# SERVODENGEN_ver2.net
KiCad netlist of a schematic drawn in EAGLE
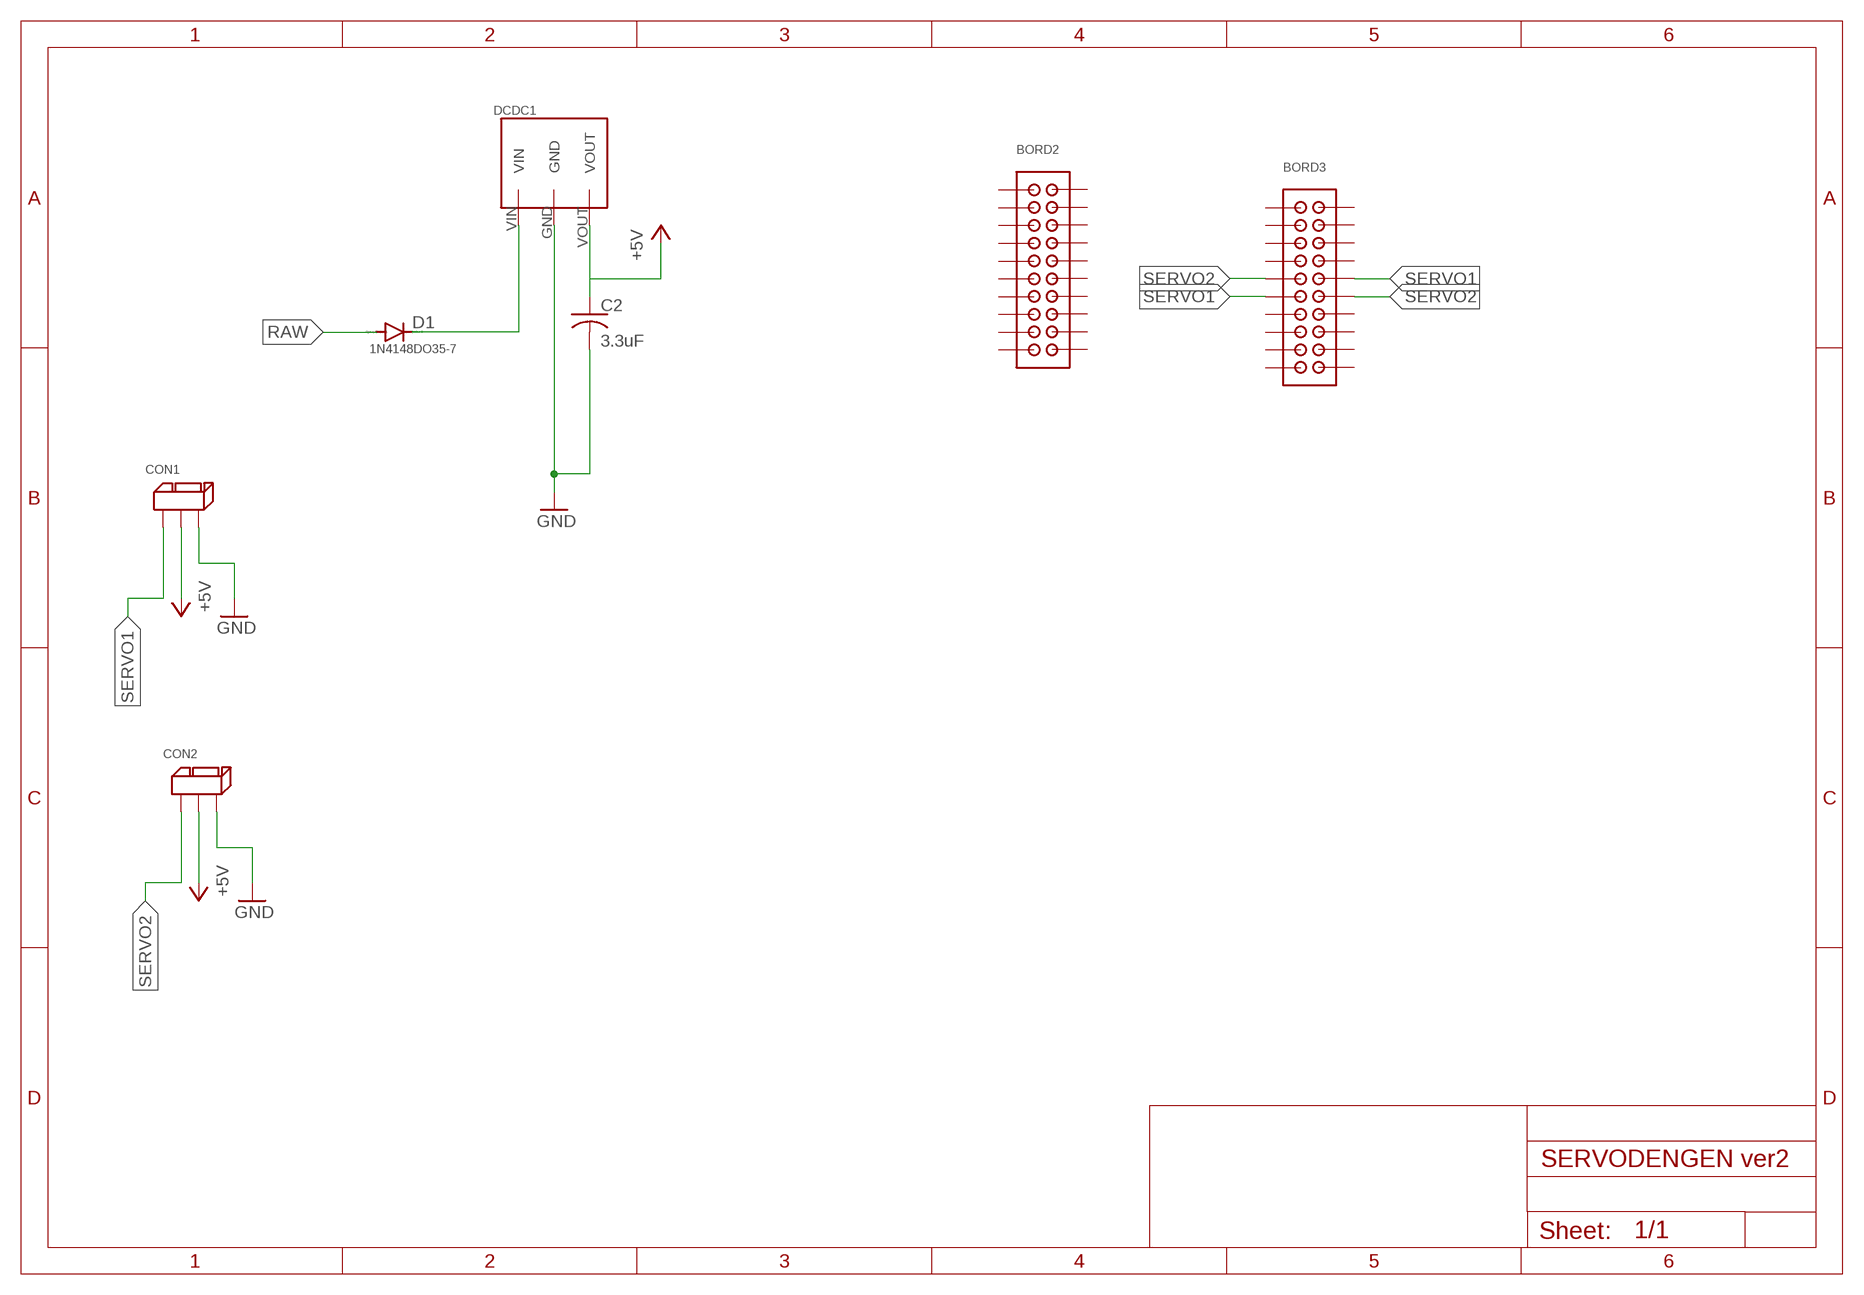
[diagram p0: schematic, sheet 1]

(export (version "E")
  (design (tool "Eeschema 10.0.6"))
  (components
    (comp (ref "BORD2")
      (value "2X10")
      (footprint "eagle-import:2X10")
      (libsource (lib "eagle-import") (part "2X10"))
    )
    (comp (ref "BORD3")
      (value "2X10")
      (footprint "eagle-import:2X10")
      (libsource (lib "eagle-import") (part "2X10"))
    )
    (comp (ref "C2")
      (value "3.3uF")
      (footprint "eagle-import:C0603")
      (libsource (lib "eagle-import") (part "C-USC0603"))
    )
    (comp (ref "CON1")
      (value "3PIN")
      (footprint "eagle-import:3PIN")
      (libsource (lib "eagle-import") (part "3PIN"))
    )
    (comp (ref "CON2")
      (value "3PIN")
      (footprint "eagle-import:3PIN")
      (libsource (lib "eagle-import") (part "3PIN"))
    )
    (comp (ref "D1")
      (value "1N4148DO35-7")
      (footprint "eagle-import:DO35-7")
      (libsource (lib "eagle-import") (part "1N4148DO35-7"))
    )
    (comp (ref "DCDC1")
      (value "5V1A_M78AR05-1")
      (footprint "eagle-import:5V1A_M78AR05-1")
      (libsource (lib "eagle-import") (part "5V1A_M78AR05-1"))
    )
  )
  (nets
    (net (code "1") (name "+5V") (class "Default")
      (node (ref "C2") (pin "1") (pinfunction "1_1") (pintype "passive"))
      (node (ref "CON1") (pin "P$2") (pinfunction "P$2_P$2") (pintype "bidirectional"))
      (node (ref "CON2") (pin "P$2") (pinfunction "P$2_P$2") (pintype "bidirectional"))
      (node (ref "DCDC1") (pin "VOUT") (pinfunction "VOUT_VOUT") (pintype "bidirectional"))
    )
    (net (code "2") (name "GND") (class "Default")
      (node (ref "C2") (pin "2") (pinfunction "2_2") (pintype "passive"))
      (node (ref "CON1") (pin "P$3") (pinfunction "P$3_P$3") (pintype "bidirectional"))
      (node (ref "CON2") (pin "P$3") (pinfunction "P$3_P$3") (pintype "bidirectional"))
      (node (ref "DCDC1") (pin "GND") (pinfunction "GND_GND") (pintype "bidirectional"))
    )
    (net (code "3") (name "RAW") (class "Default")
      (node (ref "D1") (pin "C") (pinfunction "C_C") (pintype "passive"))
      (node (ref "DCDC1") (pin "VIN") (pinfunction "VIN_VIN") (pintype "bidirectional"))
    )
    (net (code "4") (name "SERVO1") (class "Default")
      (node (ref "BORD3") (pin "P$10") (pinfunction "P$10_P$10") (pintype "bidirectional"))
      (node (ref "BORD3") (pin "P$11") (pinfunction "P$11_P$11") (pintype "bidirectional"))
      (node (ref "CON1") (pin "P$1") (pinfunction "P$1_P$1") (pintype "bidirectional"))
    )
    (net (code "5") (name "SERVO2") (class "Default")
      (node (ref "BORD3") (pin "P$12") (pinfunction "P$12_P$12") (pintype "bidirectional"))
      (node (ref "BORD3") (pin "P$9") (pinfunction "P$9_P$9") (pintype "bidirectional"))
      (node (ref "CON2") (pin "P$1") (pinfunction "P$1_P$1") (pintype "bidirectional"))
    )
    (net (code "6") (name "unconnected-(BORD2-PadP$1)") (class "Default")
      (node (ref "BORD2") (pin "P$1") (pinfunction "P$1_P$1") (pintype "bidirectional"))
    )
    (net (code "7") (name "unconnected-(BORD2-PadP$2)") (class "Default")
      (node (ref "BORD2") (pin "P$2") (pinfunction "P$2_P$2") (pintype "bidirectional"))
    )
    (net (code "8") (name "unconnected-(BORD2-PadP$3)") (class "Default")
      (node (ref "BORD2") (pin "P$3") (pinfunction "P$3_P$3") (pintype "bidirectional"))
    )
    (net (code "9") (name "unconnected-(BORD2-PadP$4)") (class "Default")
      (node (ref "BORD2") (pin "P$4") (pinfunction "P$4_P$4") (pintype "bidirectional"))
    )
    (net (code "10") (name "unconnected-(BORD2-PadP$5)") (class "Default")
      (node (ref "BORD2") (pin "P$5") (pinfunction "P$5_P$5") (pintype "bidirectional"))
    )
    (net (code "11") (name "unconnected-(BORD2-PadP$6)") (class "Default")
      (node (ref "BORD2") (pin "P$6") (pinfunction "P$6_P$6") (pintype "bidirectional"))
    )
    (net (code "12") (name "unconnected-(BORD2-PadP$7)") (class "Default")
      (node (ref "BORD2") (pin "P$7") (pinfunction "P$7_P$7") (pintype "bidirectional"))
    )
    (net (code "13") (name "unconnected-(BORD2-PadP$8)") (class "Default")
      (node (ref "BORD2") (pin "P$8") (pinfunction "P$8_P$8") (pintype "bidirectional"))
    )
    (net (code "14") (name "unconnected-(BORD2-PadP$9)") (class "Default")
      (node (ref "BORD2") (pin "P$9") (pinfunction "P$9_P$9") (pintype "bidirectional"))
    )
    (net (code "15") (name "unconnected-(BORD2-PadP$10)") (class "Default")
      (node (ref "BORD2") (pin "P$10") (pinfunction "P$10_P$10") (pintype "bidirectional"))
    )
    (net (code "16") (name "unconnected-(BORD2-PadP$11)") (class "Default")
      (node (ref "BORD2") (pin "P$11") (pinfunction "P$11_P$11") (pintype "bidirectional"))
    )
    (net (code "17") (name "unconnected-(BORD2-PadP$12)") (class "Default")
      (node (ref "BORD2") (pin "P$12") (pinfunction "P$12_P$12") (pintype "bidirectional"))
    )
    (net (code "18") (name "unconnected-(BORD2-PadP$13)") (class "Default")
      (node (ref "BORD2") (pin "P$13") (pinfunction "P$13_P$13") (pintype "bidirectional"))
    )
    (net (code "19") (name "unconnected-(BORD2-PadP$14)") (class "Default")
      (node (ref "BORD2") (pin "P$14") (pinfunction "P$14_P$14") (pintype "bidirectional"))
    )
    (net (code "20") (name "unconnected-(BORD2-PadP$15)") (class "Default")
      (node (ref "BORD2") (pin "P$15") (pinfunction "P$15_P$15") (pintype "bidirectional"))
    )
    (net (code "21") (name "unconnected-(BORD2-PadP$16)") (class "Default")
      (node (ref "BORD2") (pin "P$16") (pinfunction "P$16_P$16") (pintype "bidirectional"))
    )
    (net (code "22") (name "unconnected-(BORD2-PadP$17)") (class "Default")
      (node (ref "BORD2") (pin "P$17") (pinfunction "P$17_P$17") (pintype "bidirectional"))
    )
    (net (code "23") (name "unconnected-(BORD2-PadP$18)") (class "Default")
      (node (ref "BORD2") (pin "P$18") (pinfunction "P$18_P$18") (pintype "bidirectional"))
    )
    (net (code "24") (name "unconnected-(BORD2-PadP$19)") (class "Default")
      (node (ref "BORD2") (pin "P$19") (pinfunction "P$19_P$19") (pintype "bidirectional"))
    )
    (net (code "25") (name "unconnected-(BORD2-PadP$20)") (class "Default")
      (node (ref "BORD2") (pin "P$20") (pinfunction "P$20_P$20") (pintype "bidirectional"))
    )
    (net (code "26") (name "unconnected-(BORD3-PadP$1)") (class "Default")
      (node (ref "BORD3") (pin "P$1") (pinfunction "P$1_P$1") (pintype "bidirectional"))
    )
    (net (code "27") (name "unconnected-(BORD3-PadP$2)") (class "Default")
      (node (ref "BORD3") (pin "P$2") (pinfunction "P$2_P$2") (pintype "bidirectional"))
    )
    (net (code "28") (name "unconnected-(BORD3-PadP$3)") (class "Default")
      (node (ref "BORD3") (pin "P$3") (pinfunction "P$3_P$3") (pintype "bidirectional"))
    )
    (net (code "29") (name "unconnected-(BORD3-PadP$4)") (class "Default")
      (node (ref "BORD3") (pin "P$4") (pinfunction "P$4_P$4") (pintype "bidirectional"))
    )
    (net (code "30") (name "unconnected-(BORD3-PadP$5)") (class "Default")
      (node (ref "BORD3") (pin "P$5") (pinfunction "P$5_P$5") (pintype "bidirectional"))
    )
    (net (code "31") (name "unconnected-(BORD3-PadP$6)") (class "Default")
      (node (ref "BORD3") (pin "P$6") (pinfunction "P$6_P$6") (pintype "bidirectional"))
    )
    (net (code "32") (name "unconnected-(BORD3-PadP$7)") (class "Default")
      (node (ref "BORD3") (pin "P$7") (pinfunction "P$7_P$7") (pintype "bidirectional"))
    )
    (net (code "33") (name "unconnected-(BORD3-PadP$8)") (class "Default")
      (node (ref "BORD3") (pin "P$8") (pinfunction "P$8_P$8") (pintype "bidirectional"))
    )
    (net (code "34") (name "unconnected-(BORD3-PadP$13)") (class "Default")
      (node (ref "BORD3") (pin "P$13") (pinfunction "P$13_P$13") (pintype "bidirectional"))
    )
    (net (code "35") (name "unconnected-(BORD3-PadP$14)") (class "Default")
      (node (ref "BORD3") (pin "P$14") (pinfunction "P$14_P$14") (pintype "bidirectional"))
    )
    (net (code "36") (name "unconnected-(BORD3-PadP$15)") (class "Default")
      (node (ref "BORD3") (pin "P$15") (pinfunction "P$15_P$15") (pintype "bidirectional"))
    )
    (net (code "37") (name "unconnected-(BORD3-PadP$16)") (class "Default")
      (node (ref "BORD3") (pin "P$16") (pinfunction "P$16_P$16") (pintype "bidirectional"))
    )
    (net (code "38") (name "unconnected-(BORD3-PadP$17)") (class "Default")
      (node (ref "BORD3") (pin "P$17") (pinfunction "P$17_P$17") (pintype "bidirectional"))
    )
    (net (code "39") (name "unconnected-(BORD3-PadP$18)") (class "Default")
      (node (ref "BORD3") (pin "P$18") (pinfunction "P$18_P$18") (pintype "bidirectional"))
    )
    (net (code "40") (name "unconnected-(BORD3-PadP$19)") (class "Default")
      (node (ref "BORD3") (pin "P$19") (pinfunction "P$19_P$19") (pintype "bidirectional"))
    )
    (net (code "41") (name "unconnected-(BORD3-PadP$20)") (class "Default")
      (node (ref "BORD3") (pin "P$20") (pinfunction "P$20_P$20") (pintype "bidirectional"))
    )
    (net (code "42") (name "unconnected-(D1-PadA)") (class "Default")
      (node (ref "D1") (pin "A") (pinfunction "A_A") (pintype "passive"))
    )
  )
)
